# PWM_PULSE.net
KiCad netlist of a schematic drawn in Altium Designer
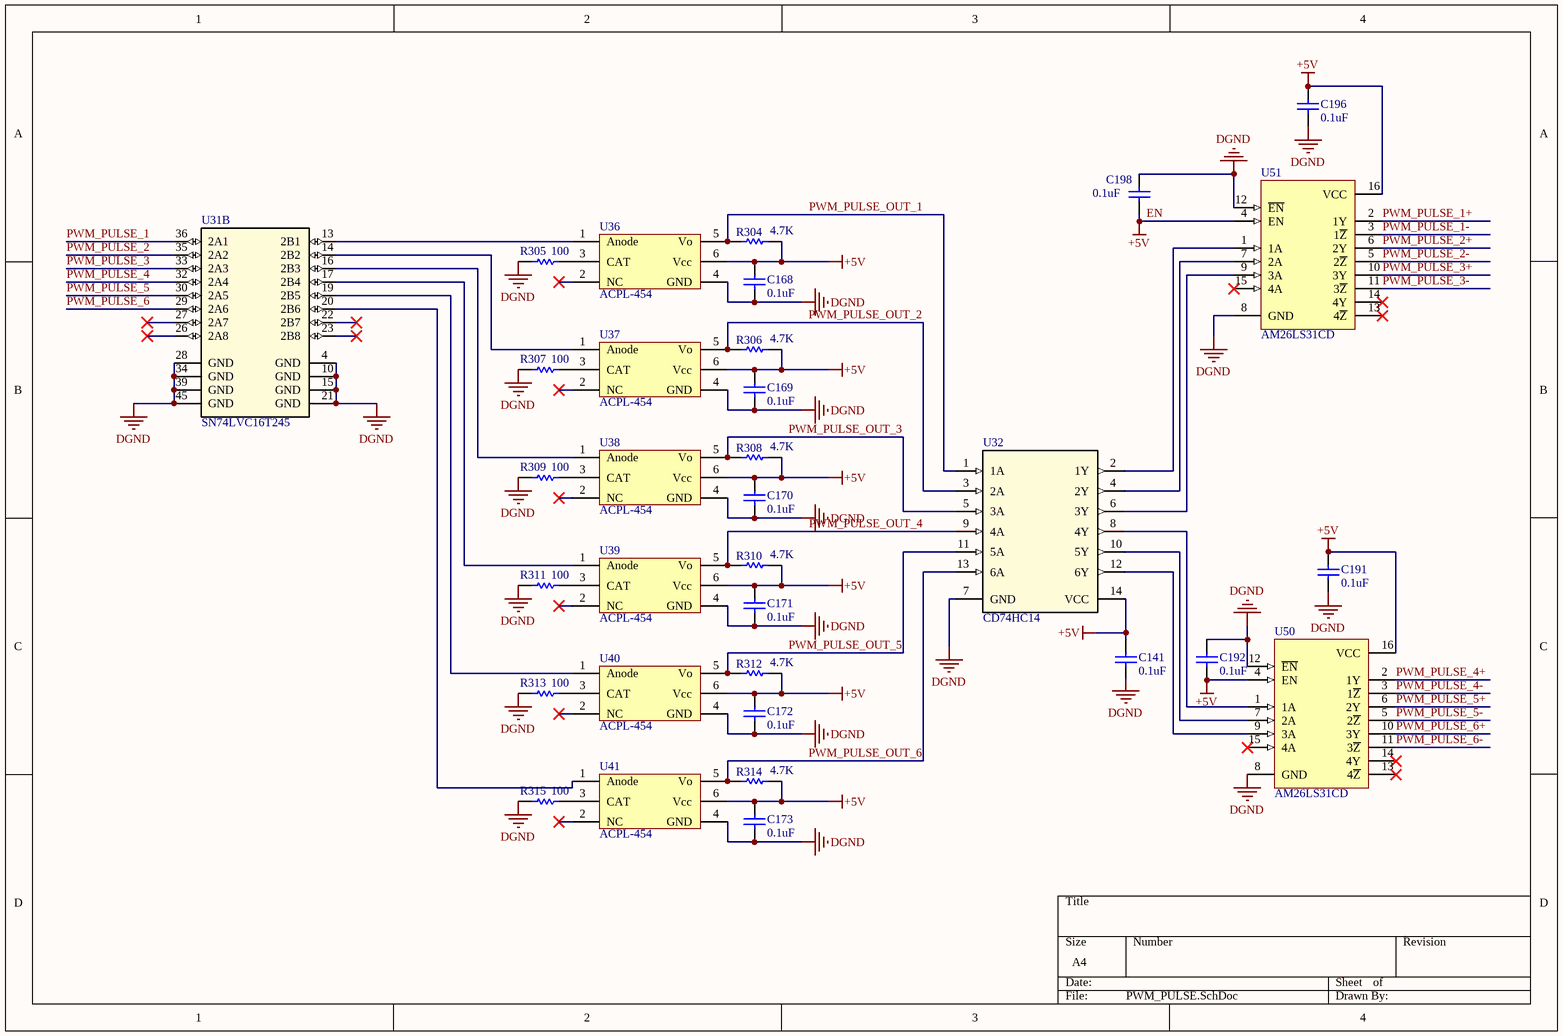
[diagram p0: PWM_PULSE.SchDoc]

(export (version "E")
  (design (tool "Eeschema 10.0.6"))
  (components
    (comp (ref "C141")
      (value "0.1uF")
      (footprint "1608[0603]")
      (description "Capacitor")
      (fields (field (name "Comment") "Cap") (field (name "PUBLISHER") "Altium Limited"))
      (libsource (lib "Miscellaneous Devices") (part "Cap"))
    )
    (comp (ref "C168")
      (value "0.1uF")
      (footprint "1608[0603]")
      (description "Capacitor")
      (fields (field (name "Comment") "Cap") (field (name "PUBLISHER") "Altium Limited"))
      (libsource (lib "Miscellaneous Devices") (part "Cap"))
    )
    (comp (ref "C169")
      (value "0.1uF")
      (footprint "1608[0603]")
      (description "Capacitor")
      (fields (field (name "Comment") "Cap") (field (name "PUBLISHER") "Altium Limited"))
      (libsource (lib "Miscellaneous Devices") (part "Cap"))
    )
    (comp (ref "C170")
      (value "0.1uF")
      (footprint "1608[0603]")
      (description "Capacitor")
      (fields (field (name "Comment") "Cap") (field (name "PUBLISHER") "Altium Limited"))
      (libsource (lib "Miscellaneous Devices") (part "Cap"))
    )
    (comp (ref "C171")
      (value "0.1uF")
      (footprint "1608[0603]")
      (description "Capacitor")
      (fields (field (name "Comment") "Cap") (field (name "PUBLISHER") "Altium Limited"))
      (libsource (lib "Miscellaneous Devices") (part "Cap"))
    )
    (comp (ref "C172")
      (value "0.1uF")
      (footprint "1608[0603]")
      (description "Capacitor")
      (fields (field (name "Comment") "Cap") (field (name "PUBLISHER") "Altium Limited"))
      (libsource (lib "Miscellaneous Devices") (part "Cap"))
    )
    (comp (ref "C173")
      (value "0.1uF")
      (footprint "1608[0603]")
      (description "Capacitor")
      (fields (field (name "Comment") "Cap") (field (name "PUBLISHER") "Altium Limited"))
      (libsource (lib "Miscellaneous Devices") (part "Cap"))
    )
    (comp (ref "C191")
      (value "0.1uF")
      (footprint "1608[0603]")
      (description "Capacitor")
      (fields (field (name "Comment") "Cap") (field (name "PUBLISHER") "Altium Limited"))
      (libsource (lib "Miscellaneous Devices") (part "Cap"))
    )
    (comp (ref "C192")
      (value "0.1uF")
      (footprint "1608[0603]")
      (description "Capacitor")
      (fields (field (name "Comment") "Cap") (field (name "PUBLISHER") "Altium Limited"))
      (libsource (lib "Miscellaneous Devices") (part "Cap"))
    )
    (comp (ref "C196")
      (value "0.1uF")
      (footprint "1608[0603]")
      (description "Capacitor")
      (fields (field (name "Comment") "Cap") (field (name "PUBLISHER") "Altium Limited"))
      (libsource (lib "Miscellaneous Devices") (part "Cap"))
    )
    (comp (ref "C198")
      (value "0.1uF")
      (footprint "1608[0603]")
      (description "Capacitor")
      (fields (field (name "Comment") "Cap") (field (name "PUBLISHER") "Altium Limited"))
      (libsource (lib "Miscellaneous Devices") (part "Cap"))
    )
    (comp (ref "R304")
      (value "4.7K")
      (footprint "1608[0603]")
      (description "Resistor")
      (fields (field (name "Comment") "Res1") (field (name "PUBLISHER") "Altium Limited"))
      (libsource (lib "Miscellaneous Devices") (part "Res1"))
    )
    (comp (ref "R305")
      (value "100")
      (footprint "1608[0603]")
      (description "Resistor")
      (fields (field (name "Comment") "Res1") (field (name "PUBLISHER") "Altium Limited"))
      (libsource (lib "Miscellaneous Devices") (part "Res1"))
    )
    (comp (ref "R306")
      (value "4.7K")
      (footprint "1608[0603]")
      (description "Resistor")
      (fields (field (name "Comment") "Res1") (field (name "PUBLISHER") "Altium Limited"))
      (libsource (lib "Miscellaneous Devices") (part "Res1"))
    )
    (comp (ref "R307")
      (value "100")
      (footprint "1608[0603]")
      (description "Resistor")
      (fields (field (name "Comment") "Res1") (field (name "PUBLISHER") "Altium Limited"))
      (libsource (lib "Miscellaneous Devices") (part "Res1"))
    )
    (comp (ref "R308")
      (value "4.7K")
      (footprint "1608[0603]")
      (description "Resistor")
      (fields (field (name "Comment") "Res1") (field (name "PUBLISHER") "Altium Limited"))
      (libsource (lib "Miscellaneous Devices") (part "Res1"))
    )
    (comp (ref "R309")
      (value "100")
      (footprint "1608[0603]")
      (description "Resistor")
      (fields (field (name "Comment") "Res1") (field (name "PUBLISHER") "Altium Limited"))
      (libsource (lib "Miscellaneous Devices") (part "Res1"))
    )
    (comp (ref "R310")
      (value "4.7K")
      (footprint "1608[0603]")
      (description "Resistor")
      (fields (field (name "Comment") "Res1") (field (name "PUBLISHER") "Altium Limited"))
      (libsource (lib "Miscellaneous Devices") (part "Res1"))
    )
    (comp (ref "R311")
      (value "100")
      (footprint "1608[0603]")
      (description "Resistor")
      (fields (field (name "Comment") "Res1") (field (name "PUBLISHER") "Altium Limited"))
      (libsource (lib "Miscellaneous Devices") (part "Res1"))
    )
    (comp (ref "R312")
      (value "4.7K")
      (footprint "1608[0603]")
      (description "Resistor")
      (fields (field (name "Comment") "Res1") (field (name "PUBLISHER") "Altium Limited"))
      (libsource (lib "Miscellaneous Devices") (part "Res1"))
    )
    (comp (ref "R313")
      (value "100")
      (footprint "1608[0603]")
      (description "Resistor")
      (fields (field (name "Comment") "Res1") (field (name "PUBLISHER") "Altium Limited"))
      (libsource (lib "Miscellaneous Devices") (part "Res1"))
    )
    (comp (ref "R314")
      (value "4.7K")
      (footprint "1608[0603]")
      (description "Resistor")
      (fields (field (name "Comment") "Res1") (field (name "PUBLISHER") "Altium Limited"))
      (libsource (lib "Miscellaneous Devices") (part "Res1"))
    )
    (comp (ref "R315")
      (value "100")
      (footprint "1608[0603]")
      (description "Resistor")
      (fields (field (name "Comment") "Res1") (field (name "PUBLISHER") "Altium Limited"))
      (libsource (lib "Miscellaneous Devices") (part "Res1"))
    )
    (comp (ref "U31")
      (value "SN74LVC16T245")
      (footprint "SN74LVC16T245_TSSOP")
      (libsource (lib "DSP_FPGA_Lib") (part "SN74LVC16T245_A"))
    )
    (comp (ref "U32")
      (value "CD74HC14")
      (footprint "CD74HC14_SOIC")
      (fields (field (name "MANUFACTURER") "Texas Instruments"))
      (libsource (lib "DSP_FPGA_Lib") (part "CD74HC14"))
    )
    (comp (ref "U36")
      (value "ACPL-454")
      (footprint "ACPL-P454")
      (libsource (lib "DSP_FPGA_Lib") (part "ACPL-454"))
    )
    (comp (ref "U37")
      (value "ACPL-454")
      (footprint "ACPL-P454")
      (libsource (lib "DSP_FPGA_Lib") (part "ACPL-454"))
    )
    (comp (ref "U38")
      (value "ACPL-454")
      (footprint "ACPL-P454")
      (libsource (lib "DSP_FPGA_Lib") (part "ACPL-454"))
    )
    (comp (ref "U39")
      (value "ACPL-454")
      (footprint "ACPL-P454")
      (libsource (lib "DSP_FPGA_Lib") (part "ACPL-454"))
    )
    (comp (ref "U40")
      (value "ACPL-454")
      (footprint "ACPL-P454")
      (libsource (lib "DSP_FPGA_Lib") (part "ACPL-454"))
    )
    (comp (ref "U41")
      (value "ACPL-454")
      (footprint "ACPL-P454")
      (libsource (lib "DSP_FPGA_Lib") (part "ACPL-454"))
    )
    (comp (ref "U50")
      (value "AM26LS31CD")
      (footprint "D016_N")
      (description "Quadruple Differential Line Driver")
      (fields (field (name "PUBLISHER") "Altium Limited"))
      (libsource (lib "TI Interface Line Driver") (part "AM26LS31CD"))
    )
    (comp (ref "U51")
      (value "AM26LS31CD")
      (footprint "D016_N")
      (description "Quadruple Differential Line Driver")
      (fields (field (name "PUBLISHER") "Altium Limited"))
      (libsource (lib "TI Interface Line Driver") (part "AM26LS31CD"))
    )
  )
  (nets
    (net (code "1") (name "+5V") (class "Default")
      (node (ref "C141") (pin "2") (pinfunction "2_2") (pintype "passive"))
      (node (ref "C168") (pin "2") (pinfunction "2_2") (pintype "passive"))
      (node (ref "C169") (pin "2") (pinfunction "2_2") (pintype "passive"))
      (node (ref "C170") (pin "2") (pinfunction "2_2") (pintype "passive"))
      (node (ref "C171") (pin "2") (pinfunction "2_2") (pintype "passive"))
      (node (ref "C172") (pin "2") (pinfunction "2_2") (pintype "passive"))
      (node (ref "C173") (pin "2") (pinfunction "2_2") (pintype "passive"))
      (node (ref "C191") (pin "2") (pinfunction "2_2") (pintype "passive"))
      (node (ref "C192") (pin "1") (pinfunction "1_1") (pintype "passive"))
      (node (ref "C196") (pin "2") (pinfunction "2_2") (pintype "passive"))
      (node (ref "C198") (pin "1") (pinfunction "1_1") (pintype "passive"))
      (node (ref "R304") (pin "1") (pinfunction "1_1") (pintype "passive"))
      (node (ref "R306") (pin "1") (pinfunction "1_1") (pintype "passive"))
      (node (ref "R308") (pin "1") (pinfunction "1_1") (pintype "passive"))
      (node (ref "R310") (pin "1") (pinfunction "1_1") (pintype "passive"))
      (node (ref "R312") (pin "1") (pinfunction "1_1") (pintype "passive"))
      (node (ref "R314") (pin "1") (pinfunction "1_1") (pintype "passive"))
      (node (ref "U32") (pin "14") (pinfunction "VCC_14") (pintype "power_in"))
      (node (ref "U36") (pin "6") (pinfunction "Vcc_6") (pintype "passive"))
      (node (ref "U37") (pin "6") (pinfunction "Vcc_6") (pintype "passive"))
      (node (ref "U38") (pin "6") (pinfunction "Vcc_6") (pintype "passive"))
      (node (ref "U39") (pin "6") (pinfunction "Vcc_6") (pintype "passive"))
      (node (ref "U40") (pin "6") (pinfunction "Vcc_6") (pintype "passive"))
      (node (ref "U41") (pin "6") (pinfunction "Vcc_6") (pintype "passive"))
      (node (ref "U50") (pin "16") (pinfunction "VCC_16") (pintype "power_in"))
      (node (ref "U50") (pin "4") (pinfunction "EN_4") (pintype "input"))
      (node (ref "U51") (pin "16") (pinfunction "VCC_16") (pintype "power_in"))
      (node (ref "U51") (pin "4") (pinfunction "EN_4") (pintype "input"))
    )
    (net (code "2") (name "/PWM_PULSE_1") (class "Default")
      (node (ref "U31") (pin "36") (pinfunction "2A1_36") (pintype "bidirectional"))
    )
    (net (code "3") (name "/PWM_PULSE_1+") (class "Default")
      (node (ref "U51") (pin "2") (pinfunction "1Y_2") (pintype "tri_state"))
    )
    (net (code "4") (name "/PWM_PULSE_1-") (class "Default")
      (node (ref "U51") (pin "3") (pinfunction "1~{Z}_3") (pintype "tri_state"))
    )
    (net (code "5") (name "/PWM_PULSE_2") (class "Default")
      (node (ref "U31") (pin "35") (pinfunction "2A2_35") (pintype "bidirectional"))
    )
    (net (code "6") (name "/PWM_PULSE_2+") (class "Default")
      (node (ref "U51") (pin "6") (pinfunction "2Y_6") (pintype "tri_state"))
    )
    (net (code "7") (name "/PWM_PULSE_2-") (class "Default")
      (node (ref "U51") (pin "5") (pinfunction "2~{Z}_5") (pintype "tri_state"))
    )
    (net (code "8") (name "/PWM_PULSE_3") (class "Default")
      (node (ref "U31") (pin "33") (pinfunction "2A3_33") (pintype "bidirectional"))
    )
    (net (code "9") (name "/PWM_PULSE_3+") (class "Default")
      (node (ref "U51") (pin "10") (pinfunction "3Y_10") (pintype "tri_state"))
    )
    (net (code "10") (name "/PWM_PULSE_3-") (class "Default")
      (node (ref "U51") (pin "11") (pinfunction "3~{Z}_11") (pintype "tri_state"))
    )
    (net (code "11") (name "/PWM_PULSE_4") (class "Default")
      (node (ref "U31") (pin "32") (pinfunction "2A4_32") (pintype "bidirectional"))
    )
    (net (code "12") (name "/PWM_PULSE_4+") (class "Default")
      (node (ref "U50") (pin "2") (pinfunction "1Y_2") (pintype "tri_state"))
    )
    (net (code "13") (name "/PWM_PULSE_4-") (class "Default")
      (node (ref "U50") (pin "3") (pinfunction "1~{Z}_3") (pintype "tri_state"))
    )
    (net (code "14") (name "/PWM_PULSE_5") (class "Default")
      (node (ref "U31") (pin "30") (pinfunction "2A5_30") (pintype "bidirectional"))
    )
    (net (code "15") (name "/PWM_PULSE_5+") (class "Default")
      (node (ref "U50") (pin "6") (pinfunction "2Y_6") (pintype "tri_state"))
    )
    (net (code "16") (name "/PWM_PULSE_5-") (class "Default")
      (node (ref "U50") (pin "5") (pinfunction "2~{Z}_5") (pintype "tri_state"))
    )
    (net (code "17") (name "/PWM_PULSE_6") (class "Default")
      (node (ref "U31") (pin "29") (pinfunction "2A6_29") (pintype "bidirectional"))
    )
    (net (code "18") (name "/PWM_PULSE_6+") (class "Default")
      (node (ref "U50") (pin "10") (pinfunction "3Y_10") (pintype "tri_state"))
    )
    (net (code "19") (name "/PWM_PULSE_6-") (class "Default")
      (node (ref "U50") (pin "11") (pinfunction "3~{Z}_11") (pintype "tri_state"))
    )
    (net (code "20") (name "/PWM_PULSE_OUT_1") (class "Default")
      (node (ref "R304") (pin "2") (pinfunction "2_2") (pintype "passive"))
      (node (ref "U32") (pin "1") (pinfunction "1A_1") (pintype "input"))
      (node (ref "U36") (pin "5") (pinfunction "Vo_5") (pintype "passive"))
    )
    (net (code "21") (name "/PWM_PULSE_OUT_2") (class "Default")
      (node (ref "R306") (pin "2") (pinfunction "2_2") (pintype "passive"))
      (node (ref "U32") (pin "3") (pinfunction "2A_3") (pintype "input"))
      (node (ref "U37") (pin "5") (pinfunction "Vo_5") (pintype "passive"))
    )
    (net (code "22") (name "/PWM_PULSE_OUT_3") (class "Default")
      (node (ref "R308") (pin "2") (pinfunction "2_2") (pintype "passive"))
      (node (ref "U32") (pin "5") (pinfunction "3A_5") (pintype "input"))
      (node (ref "U38") (pin "5") (pinfunction "Vo_5") (pintype "passive"))
    )
    (net (code "23") (name "/PWM_PULSE_OUT_4") (class "Default")
      (node (ref "R310") (pin "2") (pinfunction "2_2") (pintype "passive"))
      (node (ref "U32") (pin "9") (pinfunction "4A_9") (pintype "input"))
      (node (ref "U39") (pin "5") (pinfunction "Vo_5") (pintype "passive"))
    )
    (net (code "24") (name "/PWM_PULSE_OUT_5") (class "Default")
      (node (ref "R312") (pin "2") (pinfunction "2_2") (pintype "passive"))
      (node (ref "U32") (pin "11") (pinfunction "5A_11") (pintype "input"))
      (node (ref "U40") (pin "5") (pinfunction "Vo_5") (pintype "passive"))
    )
    (net (code "25") (name "/PWM_PULSE_OUT_6") (class "Default")
      (node (ref "R314") (pin "2") (pinfunction "2_2") (pintype "passive"))
      (node (ref "U32") (pin "13") (pinfunction "6A_13") (pintype "input"))
      (node (ref "U41") (pin "5") (pinfunction "Vo_5") (pintype "passive"))
    )
    (net (code "26") (name "DGND") (class "Default")
      (node (ref "C141") (pin "1") (pinfunction "1_1") (pintype "passive"))
      (node (ref "C168") (pin "1") (pinfunction "1_1") (pintype "passive"))
      (node (ref "C169") (pin "1") (pinfunction "1_1") (pintype "passive"))
      (node (ref "C170") (pin "1") (pinfunction "1_1") (pintype "passive"))
      (node (ref "C171") (pin "1") (pinfunction "1_1") (pintype "passive"))
      (node (ref "C172") (pin "1") (pinfunction "1_1") (pintype "passive"))
      (node (ref "C173") (pin "1") (pinfunction "1_1") (pintype "passive"))
      (node (ref "C191") (pin "1") (pinfunction "1_1") (pintype "passive"))
      (node (ref "C192") (pin "2") (pinfunction "2_2") (pintype "passive"))
      (node (ref "C196") (pin "1") (pinfunction "1_1") (pintype "passive"))
      (node (ref "C198") (pin "2") (pinfunction "2_2") (pintype "passive"))
      (node (ref "R305") (pin "2") (pinfunction "2_2") (pintype "passive"))
      (node (ref "R307") (pin "2") (pinfunction "2_2") (pintype "passive"))
      (node (ref "R309") (pin "2") (pinfunction "2_2") (pintype "passive"))
      (node (ref "R311") (pin "2") (pinfunction "2_2") (pintype "passive"))
      (node (ref "R313") (pin "2") (pinfunction "2_2") (pintype "passive"))
      (node (ref "R315") (pin "2") (pinfunction "2_2") (pintype "passive"))
      (node (ref "U31") (pin "10") (pinfunction "GND_10") (pintype "power_in"))
      (node (ref "U31") (pin "15") (pinfunction "GND_15") (pintype "power_in"))
      (node (ref "U31") (pin "21") (pinfunction "GND_21") (pintype "power_in"))
      (node (ref "U31") (pin "28") (pinfunction "GND_28") (pintype "power_in"))
      (node (ref "U31") (pin "34") (pinfunction "GND_34") (pintype "power_in"))
      (node (ref "U31") (pin "39") (pinfunction "GND_39") (pintype "power_in"))
      (node (ref "U31") (pin "4") (pinfunction "GND_4") (pintype "power_in"))
      (node (ref "U31") (pin "45") (pinfunction "GND_45") (pintype "power_in"))
      (node (ref "U32") (pin "7") (pinfunction "GND_7") (pintype "power_in"))
      (node (ref "U36") (pin "4") (pinfunction "GND_4") (pintype "passive"))
      (node (ref "U37") (pin "4") (pinfunction "GND_4") (pintype "passive"))
      (node (ref "U38") (pin "4") (pinfunction "GND_4") (pintype "passive"))
      (node (ref "U39") (pin "4") (pinfunction "GND_4") (pintype "passive"))
      (node (ref "U40") (pin "4") (pinfunction "GND_4") (pintype "passive"))
      (node (ref "U41") (pin "4") (pinfunction "GND_4") (pintype "passive"))
      (node (ref "U50") (pin "12") (pinfunction "~{EN}_12") (pintype "input"))
      (node (ref "U50") (pin "8") (pinfunction "GND_8") (pintype "power_in"))
      (node (ref "U51") (pin "12") (pinfunction "~{EN}_12") (pintype "input"))
      (node (ref "U51") (pin "8") (pinfunction "GND_8") (pintype "power_in"))
    )
    (net (code "27") (name "Net-(U31B-2B1)") (class "Default")
      (node (ref "U31") (pin "13") (pinfunction "2B1_13") (pintype "bidirectional"))
      (node (ref "U36") (pin "1") (pinfunction "Anode_1") (pintype "passive"))
    )
    (net (code "28") (name "Net-(U31B-2B2)") (class "Default")
      (node (ref "U31") (pin "14") (pinfunction "2B2_14") (pintype "bidirectional"))
      (node (ref "U37") (pin "1") (pinfunction "Anode_1") (pintype "passive"))
    )
    (net (code "29") (name "Net-(U31B-2B3)") (class "Default")
      (node (ref "U31") (pin "16") (pinfunction "2B3_16") (pintype "bidirectional"))
      (node (ref "U38") (pin "1") (pinfunction "Anode_1") (pintype "passive"))
    )
    (net (code "30") (name "Net-(U31B-2B4)") (class "Default")
      (node (ref "U31") (pin "17") (pinfunction "2B4_17") (pintype "bidirectional"))
      (node (ref "U39") (pin "1") (pinfunction "Anode_1") (pintype "passive"))
    )
    (net (code "31") (name "Net-(U31B-2B5)") (class "Default")
      (node (ref "U31") (pin "19") (pinfunction "2B5_19") (pintype "bidirectional"))
      (node (ref "U40") (pin "1") (pinfunction "Anode_1") (pintype "passive"))
    )
    (net (code "32") (name "Net-(U31B-2B6)") (class "Default")
      (node (ref "U31") (pin "20") (pinfunction "2B6_20") (pintype "bidirectional"))
      (node (ref "U41") (pin "1") (pinfunction "Anode_1") (pintype "passive"))
    )
    (net (code "33") (name "Net-(U32-1Y)") (class "Default")
      (node (ref "U32") (pin "2") (pinfunction "1Y_2") (pintype "output"))
      (node (ref "U51") (pin "1") (pinfunction "1A_1") (pintype "input"))
    )
    (net (code "34") (name "Net-(U32-2Y)") (class "Default")
      (node (ref "U32") (pin "4") (pinfunction "2Y_4") (pintype "output"))
      (node (ref "U51") (pin "7") (pinfunction "2A_7") (pintype "input"))
    )
    (net (code "35") (name "Net-(U32-3Y)") (class "Default")
      (node (ref "U32") (pin "6") (pinfunction "3Y_6") (pintype "output"))
      (node (ref "U51") (pin "9") (pinfunction "3A_9") (pintype "input"))
    )
    (net (code "36") (name "Net-(U32-4Y)") (class "Default")
      (node (ref "U32") (pin "8") (pinfunction "4Y_8") (pintype "output"))
      (node (ref "U50") (pin "1") (pinfunction "1A_1") (pintype "input"))
    )
    (net (code "37") (name "Net-(U32-5Y)") (class "Default")
      (node (ref "U32") (pin "10") (pinfunction "5Y_10") (pintype "output"))
      (node (ref "U50") (pin "7") (pinfunction "2A_7") (pintype "input"))
    )
    (net (code "38") (name "Net-(U32-6Y)") (class "Default")
      (node (ref "U32") (pin "12") (pinfunction "6Y_12") (pintype "output"))
      (node (ref "U50") (pin "9") (pinfunction "3A_9") (pintype "input"))
    )
    (net (code "39") (name "Net-(U36-CAT)") (class "Default")
      (node (ref "R305") (pin "1") (pinfunction "1_1") (pintype "passive"))
      (node (ref "U36") (pin "3") (pinfunction "CAT_3") (pintype "passive"))
    )
    (net (code "40") (name "Net-(U37-CAT)") (class "Default")
      (node (ref "R307") (pin "1") (pinfunction "1_1") (pintype "passive"))
      (node (ref "U37") (pin "3") (pinfunction "CAT_3") (pintype "passive"))
    )
    (net (code "41") (name "Net-(U38-CAT)") (class "Default")
      (node (ref "R309") (pin "1") (pinfunction "1_1") (pintype "passive"))
      (node (ref "U38") (pin "3") (pinfunction "CAT_3") (pintype "passive"))
    )
    (net (code "42") (name "Net-(U39-CAT)") (class "Default")
      (node (ref "R311") (pin "1") (pinfunction "1_1") (pintype "passive"))
      (node (ref "U39") (pin "3") (pinfunction "CAT_3") (pintype "passive"))
    )
    (net (code "43") (name "Net-(U40-CAT)") (class "Default")
      (node (ref "R313") (pin "1") (pinfunction "1_1") (pintype "passive"))
      (node (ref "U40") (pin "3") (pinfunction "CAT_3") (pintype "passive"))
    )
    (net (code "44") (name "Net-(U41-CAT)") (class "Default")
      (node (ref "R315") (pin "1") (pinfunction "1_1") (pintype "passive"))
      (node (ref "U41") (pin "3") (pinfunction "CAT_3") (pintype "passive"))
    )
    (net (code "45") (name "unconnected-(U31B-2A7-Pad27)") (class "Default")
      (node (ref "U31") (pin "27") (pinfunction "2A7_27") (pintype "bidirectional+no_connect"))
    )
    (net (code "46") (name "unconnected-(U31B-2A8-Pad26)") (class "Default")
      (node (ref "U31") (pin "26") (pinfunction "2A8_26") (pintype "bidirectional+no_connect"))
    )
    (net (code "47") (name "unconnected-(U31B-2B7-Pad22)") (class "Default")
      (node (ref "U31") (pin "22") (pinfunction "2B7_22") (pintype "bidirectional+no_connect"))
    )
    (net (code "48") (name "unconnected-(U31B-2B8-Pad23)") (class "Default")
      (node (ref "U31") (pin "23") (pinfunction "2B8_23") (pintype "bidirectional+no_connect"))
    )
    (net (code "49") (name "unconnected-(U36-NC-Pad2)") (class "Default")
      (node (ref "U36") (pin "2") (pinfunction "NC_2") (pintype "passive+no_connect"))
    )
    (net (code "50") (name "unconnected-(U37-NC-Pad2)") (class "Default")
      (node (ref "U37") (pin "2") (pinfunction "NC_2") (pintype "passive+no_connect"))
    )
    (net (code "51") (name "unconnected-(U38-NC-Pad2)") (class "Default")
      (node (ref "U38") (pin "2") (pinfunction "NC_2") (pintype "passive+no_connect"))
    )
    (net (code "52") (name "unconnected-(U39-NC-Pad2)") (class "Default")
      (node (ref "U39") (pin "2") (pinfunction "NC_2") (pintype "passive+no_connect"))
    )
    (net (code "53") (name "unconnected-(U40-NC-Pad2)") (class "Default")
      (node (ref "U40") (pin "2") (pinfunction "NC_2") (pintype "passive+no_connect"))
    )
    (net (code "54") (name "unconnected-(U41-NC-Pad2)") (class "Default")
      (node (ref "U41") (pin "2") (pinfunction "NC_2") (pintype "passive+no_connect"))
    )
    (net (code "55") (name "unconnected-(U50-4A-Pad15)") (class "Default")
      (node (ref "U50") (pin "15") (pinfunction "4A_15") (pintype "input+no_connect"))
    )
    (net (code "56") (name "unconnected-(U50-4Y-Pad14)") (class "Default")
      (node (ref "U50") (pin "14") (pinfunction "4Y_14") (pintype "tri_state+no_connect"))
    )
    (net (code "57") (name "unconnected-(U50-4~{Z}-Pad13)") (class "Default")
      (node (ref "U50") (pin "13") (pinfunction "4~{Z}_13") (pintype "tri_state+no_connect"))
    )
    (net (code "58") (name "unconnected-(U51-4A-Pad15)") (class "Default")
      (node (ref "U51") (pin "15") (pinfunction "4A_15") (pintype "input+no_connect"))
    )
    (net (code "59") (name "unconnected-(U51-4Y-Pad14)") (class "Default")
      (node (ref "U51") (pin "14") (pinfunction "4Y_14") (pintype "tri_state+no_connect"))
    )
    (net (code "60") (name "unconnected-(U51-4~{Z}-Pad13)") (class "Default")
      (node (ref "U51") (pin "13") (pinfunction "4~{Z}_13") (pintype "tri_state+no_connect"))
    )
  )
)
